# new_base_sensor.net
KiCad netlist of a schematic drawn in Altium Designer
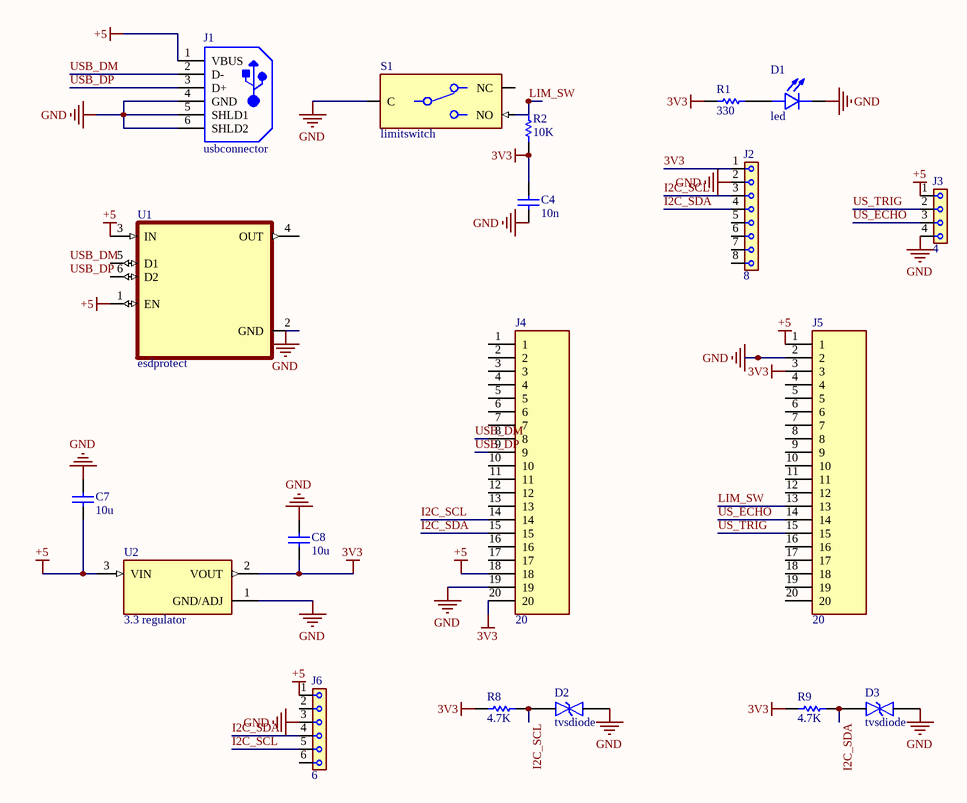
[diagram p0: new_base_sensor.SchDoc]

(export (version "E")
  (design (tool "Eeschema 10.0.6"))
  (components
    (comp (ref "C4")
      (value "10n")
      (description "Capacitor")
      (libsource (lib "Simulation Generic Components") (part "Capacitor"))
    )
    (comp (ref "C7")
      (value "10u")
      (description "Capacitor")
      (libsource (lib "Simulation Generic Components") (part "Capacitor"))
    )
    (comp (ref "C8")
      (value "10u")
      (description "Capacitor")
      (libsource (lib "Simulation Generic Components") (part "Capacitor"))
    )
    (comp (ref "D1")
      (value "led")
      (footprint "led")
      (description "Green 1.6 x 0.8 x 0.75 mm (0603) 120 潞 180 mcd Water Clear SMT LED")
      (fields (field (name "MF") "Kingbright") (field (name "MP") "APT1608VGC/A"))
      (libsource (lib "base_sensors") (part "led"))
    )
    (comp (ref "D2")
      (value "tvsdiode")
      (footprint "tvsdiode")
      (description "59V Clamp 169A (8/20Âµs) Ipp Tvs Diode Through Hole DO-201")
      (fields (field (name "MF") "STMicroelectronics") (field (name "MP") "1.5KE33CA"))
      (libsource (lib "base_sensors") (part "tvsdiode"))
    )
    (comp (ref "D3")
      (value "tvsdiode")
      (footprint "tvsdiode")
      (description "59V Clamp 169A (8/20Âµs) Ipp Tvs Diode Through Hole DO-201")
      (fields (field (name "MF") "STMicroelectronics") (field (name "MP") "1.5KE33CA"))
      (libsource (lib "base_sensors") (part "tvsdiode"))
    )
    (comp (ref "J1")
      (value "usbconnector")
      (footprint "usbconnector")
      (description "Single USB 2.0, Receptacle Connecter, B Type, 4 Position Through Hole, -55 to 85 degC, RoHS, Tray")
      (libsource (lib "Actuator_Base_Board") (part "CMP-1752-00001-1"))
    )
    (comp (ref "J2")
      (value "8")
      (footprint "8")
      (fields (field (name "MF") "WÃ¼rth Elektronik") (field (name "MP") "62001011821"))
      (libsource (lib "base_sensors") (part "8"))
    )
    (comp (ref "J3")
      (value "4")
      (footprint "4")
      (fields (field (name "MF") "WÃ¼rth Elektronik") (field (name "MP") "62001011821"))
      (libsource (lib "base_sensors") (part "4"))
    )
    (comp (ref "J4")
      (value "20")
      (footprint "20")
      (description "AMPMODU 20 Position Through-Hole Single Row Straight .100 Inch Header")
      (fields (field (name "MF") "TE Connectivity") (field (name "MP") "2-87224-0"))
      (libsource (lib "base_sensors") (part "20"))
    )
    (comp (ref "J5")
      (value "20")
      (footprint "20")
      (description "AMPMODU 20 Position Through-Hole Single Row Straight .100 Inch Header")
      (fields (field (name "MF") "TE Connectivity") (field (name "MP") "2-87224-0"))
      (libsource (lib "base_sensors") (part "20"))
    )
    (comp (ref "J6")
      (value "6")
      (footprint "6")
      (fields (field (name "MF") "WÃ¼rth Elektronik") (field (name "MP") "62001011821"))
      (libsource (lib "base_sensors") (part "6"))
    )
    (comp (ref "R1")
      (value "330")
      (description "Resistor")
      (libsource (lib "Simulation Generic Components") (part "Resistor"))
    )
    (comp (ref "R2")
      (value "10K")
      (description "Resistor")
      (libsource (lib "Simulation Generic Components") (part "Resistor"))
    )
    (comp (ref "R8")
      (value "4.7K")
      (description "Resistor")
      (libsource (lib "Simulation Generic Components") (part "Resistor"))
    )
    (comp (ref "R9")
      (value "4.7K")
      (description "Resistor")
      (libsource (lib "Simulation Generic Components") (part "Resistor"))
    )
    (comp (ref "S1")
      (value "limitswitch")
      (footprint "limitswitch")
      (description "Switch Snap Action N.O./N.C. SPDT Long Hinge Lever Solder 5A 250VAC 0.39N Screw Mount")
      (fields (field (name "MF") "Omron") (field (name "MP") "SS-5GL111"))
      (libsource (lib "base_sensors") (part "limitswitch"))
    )
    (comp (ref "U1")
      (value "esdprotect")
      (footprint "esdprotect")
      (description "Current-limit switch and D+/Dâ€“ ESD protection for USB Host")
      (fields (field (name "MF") "Texas Instruments") (field (name "MP") "TPD3S044DBVR"))
      (libsource (lib "base_sensors") (part "esdprotect"))
    )
    (comp (ref "U2")
      (value "3.3 regulator")
      (footprint "3.3regultor")
      (description "LDO Voltage Regulators 800MA LDO LINEAR REG")
      (fields (field (name "MF") "ams AG") (field (name "MP") "AMS1117-3.3"))
      (libsource (lib "base_sensors") (part "3.3 regulator"))
    )
  )
  (nets
    (net (code "1") (name "+5") (class "Default")
      (node (ref "C7") (pin "1") (pinfunction "1_1") (pintype "passive"))
      (node (ref "J1") (pin "1") (pinfunction "VBUS_1") (pintype "passive"))
      (node (ref "J3") (pin "1") (pinfunction "1_1") (pintype "passive"))
      (node (ref "J4") (pin "18") (pinfunction "18_18") (pintype "passive"))
      (node (ref "J5") (pin "1") (pinfunction "1_1") (pintype "passive"))
      (node (ref "J6") (pin "1") (pinfunction "1_1") (pintype "passive"))
      (node (ref "U1") (pin "1") (pinfunction "EN_1") (pintype "bidirectional"))
      (node (ref "U1") (pin "3") (pinfunction "IN_3") (pintype "input"))
      (node (ref "U2") (pin "3") (pinfunction "VIN_3") (pintype "input"))
    )
    (net (code "2") (name "/I2C_SCL") (class "Default")
      (node (ref "D2") (pin "1") (pinfunction "1_1") (pintype "passive"))
      (node (ref "J2") (pin "3") (pinfunction "3_3") (pintype "passive"))
      (node (ref "J4") (pin "14") (pinfunction "14_14") (pintype "passive"))
      (node (ref "J6") (pin "5") (pinfunction "5_5") (pintype "passive"))
      (node (ref "R8") (pin "2") (pinfunction "2_2") (pintype "passive"))
    )
    (net (code "3") (name "/I2C_SDA") (class "Default")
      (node (ref "D3") (pin "1") (pinfunction "1_1") (pintype "passive"))
      (node (ref "J2") (pin "4") (pinfunction "4_4") (pintype "passive"))
      (node (ref "J4") (pin "15") (pinfunction "15_15") (pintype "passive"))
      (node (ref "J6") (pin "4") (pinfunction "4_4") (pintype "passive"))
      (node (ref "R9") (pin "2") (pinfunction "2_2") (pintype "passive"))
    )
    (net (code "4") (name "/LIM_SW") (class "Default")
      (node (ref "J5") (pin "13") (pinfunction "13_13") (pintype "passive"))
      (node (ref "R2") (pin "1") (pinfunction "1_1") (pintype "passive"))
      (node (ref "S1") (pin "NO") (pinfunction "NO_NO") (pintype "input"))
    )
    (net (code "5") (name "/USB_DM") (class "Default")
      (node (ref "J1") (pin "2") (pinfunction "D-_2") (pintype "passive"))
      (node (ref "J4") (pin "8") (pinfunction "8_8") (pintype "passive"))
    )
    (net (code "6") (name "/USB_DP") (class "Default")
      (node (ref "J1") (pin "3") (pinfunction "D+_3") (pintype "passive"))
      (node (ref "J4") (pin "9") (pinfunction "9_9") (pintype "passive"))
    )
    (net (code "7") (name "/US_ECHO") (class "Default")
      (node (ref "J3") (pin "3") (pinfunction "3_3") (pintype "passive"))
      (node (ref "J5") (pin "14") (pinfunction "14_14") (pintype "passive"))
    )
    (net (code "8") (name "/US_TRIG") (class "Default")
      (node (ref "J3") (pin "2") (pinfunction "2_2") (pintype "passive"))
      (node (ref "J5") (pin "15") (pinfunction "15_15") (pintype "passive"))
    )
    (net (code "9") (name "3V3") (class "Default")
      (node (ref "C4") (pin "1") (pinfunction "1_1") (pintype "passive"))
      (node (ref "C8") (pin "1") (pinfunction "1_1") (pintype "passive"))
      (node (ref "J2") (pin "1") (pinfunction "1_1") (pintype "passive"))
      (node (ref "J4") (pin "20") (pinfunction "20_20") (pintype "passive"))
      (node (ref "J5") (pin "3") (pinfunction "3_3") (pintype "passive"))
      (node (ref "R1") (pin "1") (pinfunction "1_1") (pintype "passive"))
      (node (ref "R2") (pin "2") (pinfunction "2_2") (pintype "passive"))
      (node (ref "R8") (pin "1") (pinfunction "1_1") (pintype "passive"))
      (node (ref "R9") (pin "1") (pinfunction "1_1") (pintype "passive"))
      (node (ref "U2") (pin "2") (pinfunction "VOUT_2") (pintype "output"))
    )
    (net (code "10") (name "GND") (class "Default")
      (node (ref "C4") (pin "2") (pinfunction "2_2") (pintype "passive"))
      (node (ref "C7") (pin "2") (pinfunction "2_2") (pintype "passive"))
      (node (ref "C8") (pin "2") (pinfunction "2_2") (pintype "passive"))
      (node (ref "D1") (pin "C") (pinfunction "C_C") (pintype "passive"))
      (node (ref "D2") (pin "2") (pinfunction "2_2") (pintype "passive"))
      (node (ref "D3") (pin "2") (pinfunction "2_2") (pintype "passive"))
      (node (ref "J1") (pin "4") (pinfunction "GND_4") (pintype "passive"))
      (node (ref "J1") (pin "5") (pinfunction "SHLD1_5") (pintype "passive"))
      (node (ref "J1") (pin "6") (pinfunction "SHLD2_6") (pintype "passive"))
      (node (ref "J2") (pin "2") (pinfunction "2_2") (pintype "passive"))
      (node (ref "J3") (pin "4") (pinfunction "4_4") (pintype "passive"))
      (node (ref "J4") (pin "19") (pinfunction "19_19") (pintype "passive"))
      (node (ref "J5") (pin "2") (pinfunction "2_2") (pintype "passive"))
      (node (ref "J6") (pin "3") (pinfunction "3_3") (pintype "passive"))
      (node (ref "S1") (pin "C") (pinfunction "C_C") (pintype "bidirectional"))
      (node (ref "U1") (pin "2") (pinfunction "GND_2") (pintype "power_in"))
      (node (ref "U2") (pin "1") (pinfunction "GND/ADJ_1") (pintype "power_in"))
    )
    (net (code "11") (name "Net-(D1-PadA)") (class "Default")
      (node (ref "D1") (pin "A") (pinfunction "A_A") (pintype "passive"))
      (node (ref "R1") (pin "2") (pinfunction "2_2") (pintype "passive"))
    )
    (net (code "12") (name "unconnected-(J2-Pad5)") (class "Default")
      (node (ref "J2") (pin "5") (pinfunction "5_5") (pintype "passive"))
    )
    (net (code "13") (name "unconnected-(J2-Pad6)") (class "Default")
      (node (ref "J2") (pin "6") (pinfunction "6_6") (pintype "passive"))
    )
    (net (code "14") (name "unconnected-(J2-Pad7)") (class "Default")
      (node (ref "J2") (pin "7") (pinfunction "7_7") (pintype "passive"))
    )
    (net (code "15") (name "unconnected-(J2-Pad8)") (class "Default")
      (node (ref "J2") (pin "8") (pinfunction "8_8") (pintype "passive"))
    )
    (net (code "16") (name "unconnected-(J4-Pad1)") (class "Default")
      (node (ref "J4") (pin "1") (pinfunction "1_1") (pintype "passive"))
    )
    (net (code "17") (name "unconnected-(J4-Pad2)") (class "Default")
      (node (ref "J4") (pin "2") (pinfunction "2_2") (pintype "passive"))
    )
    (net (code "18") (name "unconnected-(J4-Pad3)") (class "Default")
      (node (ref "J4") (pin "3") (pinfunction "3_3") (pintype "passive"))
    )
    (net (code "19") (name "unconnected-(J4-Pad4)") (class "Default")
      (node (ref "J4") (pin "4") (pinfunction "4_4") (pintype "passive"))
    )
    (net (code "20") (name "unconnected-(J4-Pad5)") (class "Default")
      (node (ref "J4") (pin "5") (pinfunction "5_5") (pintype "passive"))
    )
    (net (code "21") (name "unconnected-(J4-Pad6)") (class "Default")
      (node (ref "J4") (pin "6") (pinfunction "6_6") (pintype "passive"))
    )
    (net (code "22") (name "unconnected-(J4-Pad7)") (class "Default")
      (node (ref "J4") (pin "7") (pinfunction "7_7") (pintype "passive"))
    )
    (net (code "23") (name "unconnected-(J4-Pad10)") (class "Default")
      (node (ref "J4") (pin "10") (pinfunction "10_10") (pintype "passive"))
    )
    (net (code "24") (name "unconnected-(J4-Pad11)") (class "Default")
      (node (ref "J4") (pin "11") (pinfunction "11_11") (pintype "passive"))
    )
    (net (code "25") (name "unconnected-(J4-Pad12)") (class "Default")
      (node (ref "J4") (pin "12") (pinfunction "12_12") (pintype "passive"))
    )
    (net (code "26") (name "unconnected-(J4-Pad13)") (class "Default")
      (node (ref "J4") (pin "13") (pinfunction "13_13") (pintype "passive"))
    )
    (net (code "27") (name "unconnected-(J4-Pad16)") (class "Default")
      (node (ref "J4") (pin "16") (pinfunction "16_16") (pintype "passive"))
    )
    (net (code "28") (name "unconnected-(J4-Pad17)") (class "Default")
      (node (ref "J4") (pin "17") (pinfunction "17_17") (pintype "passive"))
    )
    (net (code "29") (name "unconnected-(J5-Pad4)") (class "Default")
      (node (ref "J5") (pin "4") (pinfunction "4_4") (pintype "passive"))
    )
    (net (code "30") (name "unconnected-(J5-Pad5)") (class "Default")
      (node (ref "J5") (pin "5") (pinfunction "5_5") (pintype "passive"))
    )
    (net (code "31") (name "unconnected-(J5-Pad6)") (class "Default")
      (node (ref "J5") (pin "6") (pinfunction "6_6") (pintype "passive"))
    )
    (net (code "32") (name "unconnected-(J5-Pad7)") (class "Default")
      (node (ref "J5") (pin "7") (pinfunction "7_7") (pintype "passive"))
    )
    (net (code "33") (name "unconnected-(J5-Pad8)") (class "Default")
      (node (ref "J5") (pin "8") (pinfunction "8_8") (pintype "passive"))
    )
    (net (code "34") (name "unconnected-(J5-Pad9)") (class "Default")
      (node (ref "J5") (pin "9") (pinfunction "9_9") (pintype "passive"))
    )
    (net (code "35") (name "unconnected-(J5-Pad10)") (class "Default")
      (node (ref "J5") (pin "10") (pinfunction "10_10") (pintype "passive"))
    )
    (net (code "36") (name "unconnected-(J5-Pad11)") (class "Default")
      (node (ref "J5") (pin "11") (pinfunction "11_11") (pintype "passive"))
    )
    (net (code "37") (name "unconnected-(J5-Pad12)") (class "Default")
      (node (ref "J5") (pin "12") (pinfunction "12_12") (pintype "passive"))
    )
    (net (code "38") (name "unconnected-(J5-Pad16)") (class "Default")
      (node (ref "J5") (pin "16") (pinfunction "16_16") (pintype "passive"))
    )
    (net (code "39") (name "unconnected-(J5-Pad17)") (class "Default")
      (node (ref "J5") (pin "17") (pinfunction "17_17") (pintype "passive"))
    )
    (net (code "40") (name "unconnected-(J5-Pad18)") (class "Default")
      (node (ref "J5") (pin "18") (pinfunction "18_18") (pintype "passive"))
    )
    (net (code "41") (name "unconnected-(J5-Pad19)") (class "Default")
      (node (ref "J5") (pin "19") (pinfunction "19_19") (pintype "passive"))
    )
    (net (code "42") (name "unconnected-(J5-Pad20)") (class "Default")
      (node (ref "J5") (pin "20") (pinfunction "20_20") (pintype "passive"))
    )
    (net (code "43") (name "unconnected-(J6-Pad2)") (class "Default")
      (node (ref "J6") (pin "2") (pinfunction "2_2") (pintype "passive"))
    )
    (net (code "44") (name "unconnected-(J6-Pad6)") (class "Default")
      (node (ref "J6") (pin "6") (pinfunction "6_6") (pintype "passive"))
    )
    (net (code "45") (name "unconnected-(S1-PadNC)") (class "Default")
      (node (ref "S1") (pin "NC") (pinfunction "NC_NC") (pintype "bidirectional"))
    )
    (net (code "46") (name "unconnected-(U1-D1-Pad5)") (class "Default")
      (node (ref "U1") (pin "5") (pinfunction "D1_5") (pintype "bidirectional"))
    )
    (net (code "47") (name "unconnected-(U1-D2-Pad6)") (class "Default")
      (node (ref "U1") (pin "6") (pinfunction "D2_6") (pintype "bidirectional"))
    )
    (net (code "48") (name "unconnected-(U1-OUT-Pad4)") (class "Default")
      (node (ref "U1") (pin "4") (pinfunction "OUT_4") (pintype "output"))
    )
  )
)
